# 5V_to_3_3V.net
KiCad netlist of a schematic drawn in Altium Designer
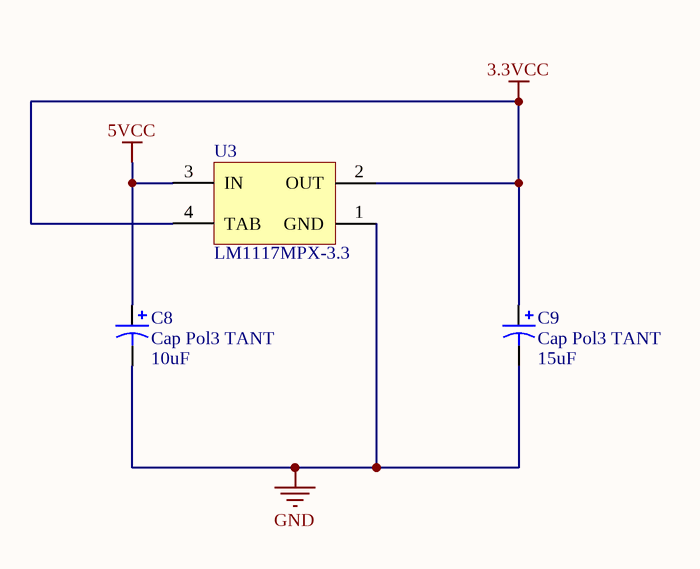
[diagram p0: 5V to 3.3V.SchDoc]

(export (version "E")
  (design (tool "Eeschema 10.0.6"))
  (components
    (comp (ref "C8")
      (value "Cap Pol3 TANT")
      (footprint "CAPC3216N")
      (description "Polarized Capacitor (Surface Mount)")
      (fields (field (name "ALTIUM_VALUE") "10uF") (field (name "PUBLISHER") "Altium Limited"))
      (libsource (lib "Miscellaneous Devices") (part "Cap Pol3"))
    )
    (comp (ref "C9")
      (value "Cap Pol3 TANT")
      (footprint "CAPC3216N")
      (description "Polarized Capacitor (Surface Mount)")
      (fields (field (name "ALTIUM_VALUE") "15uF") (field (name "PUBLISHER") "Altium Limited"))
      (libsource (lib "Miscellaneous Devices") (part "Cap Pol3"))
    )
    (comp (ref "U3")
      (value "LM1117MPX-3.3")
      (footprint "MP04A_N")
      (description "800mA Low-Dropout Linear Regulator, 4-pin SOT-223")
      (fields
        (field (name "MANUFACTURER") "National Semiconductor")
        (field (name "PUBLISHER") "Altium Limited")
      )
      (libsource (lib "NSC LDO") (part "LM1117MPX-3.3"))
    )
  )
  (nets
    (net (code "1") (name "3.3VCC") (class "Default")
      (node (ref "C9") (pin "1") (pinfunction "1_1") (pintype "passive"))
      (node (ref "U3") (pin "2") (pinfunction "OUT_2") (pintype "power_in"))
      (node (ref "U3") (pin "4") (pinfunction "TAB_4") (pintype "power_in"))
    )
    (net (code "2") (name "5VCC") (class "Default")
      (node (ref "C8") (pin "1") (pinfunction "1_1") (pintype "passive"))
      (node (ref "U3") (pin "3") (pinfunction "IN_3") (pintype "power_in"))
    )
    (net (code "3") (name "GND") (class "Default")
      (node (ref "C8") (pin "2") (pinfunction "2_2") (pintype "passive"))
      (node (ref "C9") (pin "2") (pinfunction "2_2") (pintype "passive"))
      (node (ref "U3") (pin "1") (pinfunction "GND_1") (pintype "power_in"))
    )
  )
)
